# Vref.net
KiCad netlist of a schematic drawn in Altium Designer
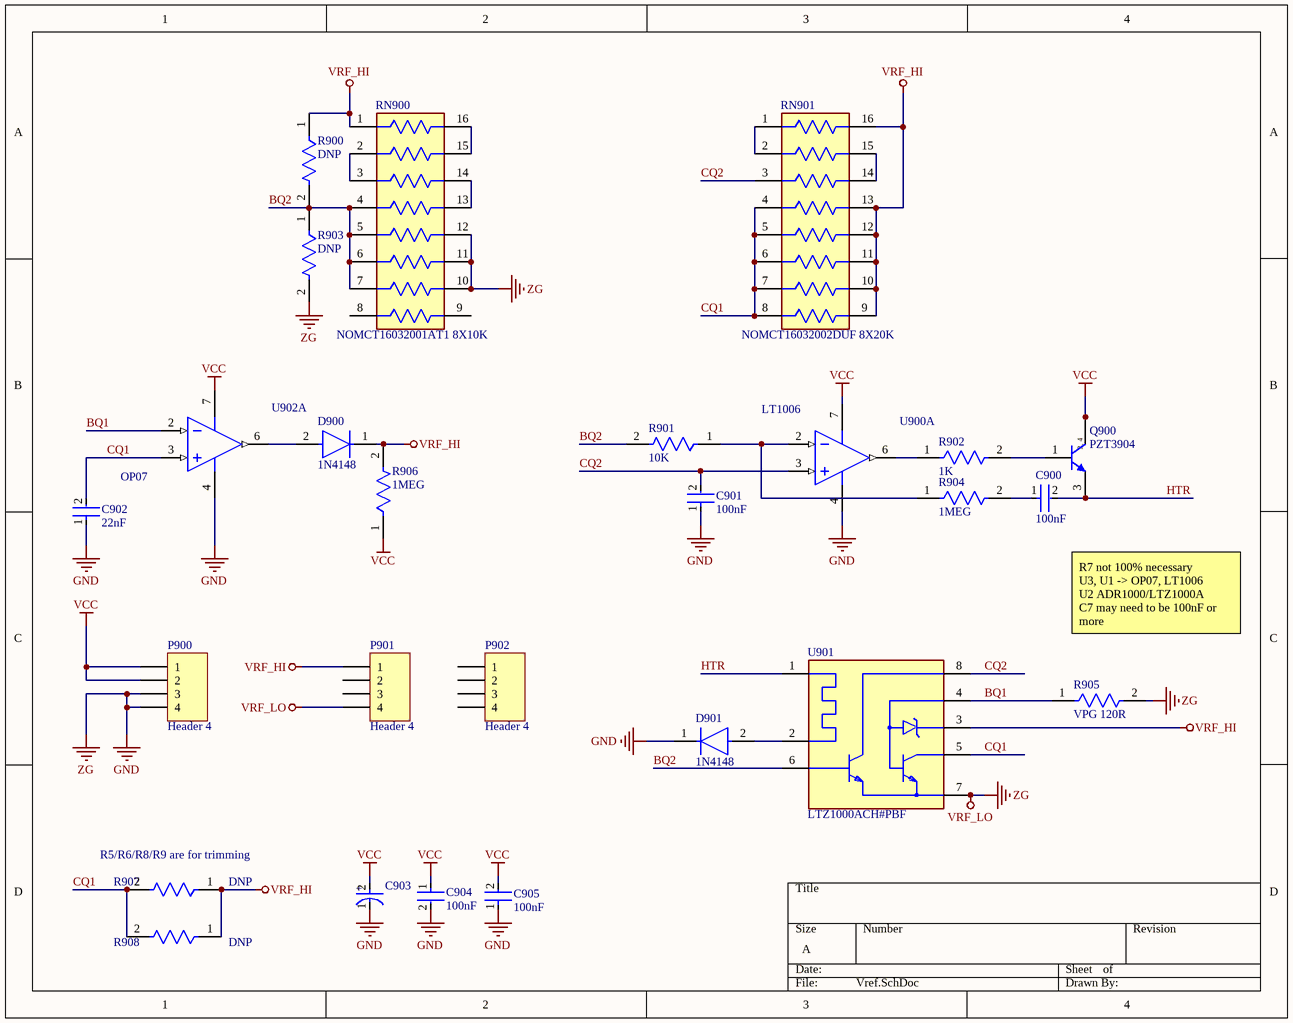
[diagram p0: Vref.SchDoc]

(export (version "E")
  (design (tool "Eeschema 10.0.6"))
  (components
    (comp (ref "C900")
      (value "100nF")
      (footprint "FP-CGA3E-0_3-0_1-IPC_B")
      (description "Cap Ceramic 100nF 50V X7R 10% Pad SMD 0603 +125°C Automotive T/R")
      (fields (field (name "TOLERANCE") "10%") (field (name "VOLTAGE") "50V"))
      (libsource (lib "Altium Content Vault") (part "b4654b650e69147ec39a6b967a45e02"))
    )
    (comp (ref "C901")
      (value "100nF")
      (footprint "FP-CGA3E-0_3-0_1-IPC_B")
      (description "Cap Ceramic 100nF 50V X7R 10% Pad SMD 0603 +125°C Automotive T/R")
      (fields (field (name "TOLERANCE") "10%") (field (name "VOLTAGE") "50V"))
      (libsource (lib "Altium Content Vault") (part "b4654b650e69147ec39a6b967a45e02"))
    )
    (comp (ref "C902")
      (value "22nF")
      (footprint "FP-CGA3E-0_3-0_1-IPC_B")
      (description "Cap Ceramic 100nF 50V X7R 10% Pad SMD 0603 +125°C Automotive T/R")
      (fields (field (name "TOLERANCE") "10%") (field (name "VOLTAGE") "50V"))
      (libsource (lib "Altium Content Vault") (part "b4654b650e69147ec39a6b967a45e02"))
    )
    (comp (ref "C903")
      (value "T491D226K025AT")
      (footprint "FP-T491D226K025AT-MFG")
      (description "CAP TANT 22UF 10% 25V 2917")
      (fields (field (name "TOLERANCE") "10%") (field (name "VOLTAGE") "25V"))
      (libsource (lib "Altium Content Vault") (part "a00bbbee19879c290e62620ae7e47b1"))
    )
    (comp (ref "C904")
      (value "100nF")
      (footprint "FP-CGA3E-0_3-0_1-IPC_B")
      (description "Cap Ceramic 100nF 50V X7R 10% Pad SMD 0603 +125°C Automotive T/R")
      (fields (field (name "TOLERANCE") "10%") (field (name "VOLTAGE") "50V"))
      (libsource (lib "Altium Content Vault") (part "b4654b650e69147ec39a6b967a45e02"))
    )
    (comp (ref "C905")
      (value "100nF")
      (footprint "FP-CGA3E-0_3-0_1-IPC_B")
      (description "Cap Ceramic 100nF 50V X7R 10% Pad SMD 0603 +125°C Automotive T/R")
      (fields (field (name "TOLERANCE") "10%") (field (name "VOLTAGE") "50V"))
      (libsource (lib "Altium Content Vault") (part "b4654b650e69147ec39a6b967a45e02"))
    )
    (comp (ref "D900")
      (value "1N4148")
      (footprint "FP-017AG-MFG")
      (description "DIODE GEN PURP 100V 200MA DO35")
      (fields (field (name "VOLTAGE") "100V"))
      (libsource (lib "Altium Content Vault") (part "d7152d700b627762746794eb795d46e"))
    )
    (comp (ref "D901")
      (value "1N4148")
      (footprint "FP-017AG-MFG")
      (description "DIODE GEN PURP 100V 200MA DO35")
      (fields (field (name "VOLTAGE") "100V"))
      (libsource (lib "Altium Content Vault") (part "d7152d700b627762746794eb795d46e"))
    )
    (comp (ref "P900")
      (value "Header 4")
      (footprint "HDR1X4")
      (description "Header, 4-Pin")
      (fields (field (name "PUBLISHER") "Altium Limited"))
      (libsource (lib "Miscellaneous Connectors") (part "Header 4"))
    )
    (comp (ref "P901")
      (value "Header 4")
      (footprint "HDR1X4")
      (description "Header, 4-Pin")
      (fields (field (name "PUBLISHER") "Altium Limited"))
      (libsource (lib "Miscellaneous Connectors") (part "Header 4"))
    )
    (comp (ref "P902")
      (value "Header 4")
      (footprint "HDR1X4")
      (description "Header, 4-Pin")
      (fields (field (name "PUBLISHER") "Altium Limited"))
      (libsource (lib "Miscellaneous Connectors") (part "Header 4"))
    )
    (comp (ref "Q900")
      (value "PZT3904")
      (footprint "FAIR-SOT223-4_V")
      (description "NPN General-Purpose Amplifier, 40 V, 200 mA, -55 to 150 degC, 4-Pin SOT223, RoHS, Tape and Reel")
      (fields (field (name "MANUFACTURER") "FairchildSemiconductor"))
      (libsource (lib "Altium Content Vault") (part "BJT-NPN-BCEC-4"))
    )
    (comp (ref "R900")
      (value "DNP")
      (footprint "FP-ERA3A-IPC_C")
      (description "RES SMD 1K OHM 0.1% 1/10W 0603")
      (fields (field (name "TOLERANCE") "0.1%"))
      (libsource (lib "Altium Content Vault") (part "1029c3af85768c4190bb7ad29bc67b5"))
    )
    (comp (ref "R901")
      (value "10K")
      (footprint "FP-ERA3A-IPC_C")
      (description "RES SMD 1K OHM 0.1% 1/10W 0603")
      (fields (field (name "TOLERANCE") "0.1%"))
      (libsource (lib "Altium Content Vault") (part "1029c3af85768c4190bb7ad29bc67b5"))
    )
    (comp (ref "R902")
      (value "1K")
      (footprint "FP-ERA3A-IPC_C")
      (description "RES SMD 1K OHM 0.1% 1/10W 0603")
      (fields (field (name "TOLERANCE") "0.1%"))
      (libsource (lib "Altium Content Vault") (part "1029c3af85768c4190bb7ad29bc67b5"))
    )
    (comp (ref "R903")
      (value "DNP")
      (footprint "FP-ERA3A-IPC_C")
      (description "RES SMD 1K OHM 0.1% 1/10W 0603")
      (fields (field (name "TOLERANCE") "0.1%"))
      (libsource (lib "Altium Content Vault") (part "1029c3af85768c4190bb7ad29bc67b5"))
    )
    (comp (ref "R904")
      (value "1MEG")
      (footprint "FP-CRCW0603-e3-IPC_A")
      (description "RES Thick Film, 1MΩ, 1%, 0.1W, 100ppm/°C, 0603")
      (fields (field (name "TOLERANCE") "1%"))
      (libsource (lib "Altium Content Vault") (part "1029c3af85768c4190bb7ad29bc67b5"))
    )
    (comp (ref "R905")
      (value "VPG 120R")
      (footprint "FP-S102K-MFG")
      (description "RES 20K OHM 0.6W 0.01% RADIAL")
      (fields (field (name "TOLERANCE") "0.01%"))
      (libsource (lib "Altium Content Vault") (part "1029c3af85768c4190bb7ad29bc67b5"))
    )
    (comp (ref "R906")
      (value "1MEG")
      (footprint "FP-CRCW0603-e3-IPC_A")
      (description "RES Thick Film, 1MΩ, 1%, 0.1W, 100ppm/°C, 0603")
      (fields (field (name "TOLERANCE") "1%"))
      (libsource (lib "Altium Content Vault") (part "1029c3af85768c4190bb7ad29bc67b5"))
    )
    (comp (ref "R907")
      (value "DNP")
      (footprint "FP-ERA3A-IPC_C")
      (description "RES SMD 1K OHM 0.1% 1/10W 0603")
      (fields (field (name "TOLERANCE") "0.1%"))
      (libsource (lib "Altium Content Vault") (part "1029c3af85768c4190bb7ad29bc67b5"))
    )
    (comp (ref "R908")
      (value "DNP")
      (footprint "FP-ERA3A-IPC_C")
      (description "RES SMD 1K OHM 0.1% 1/10W 0603")
      (fields (field (name "TOLERANCE") "0.1%"))
      (libsource (lib "Altium Content Vault") (part "1029c3af85768c4190bb7ad29bc67b5"))
    )
    (comp (ref "RN900")
      (value "NOMCT16032001AT1 8X10K")
      (footprint "FP-TDP16-MFG")
      (description "Res Thin Film NET 100K Ohm 0.5% 4/5W ±25ppm/°C ISOL Molded 16-Pin DIP Pin Thru-Hole Tube")
      (libsource (lib "Altium Content Vault") (part "611a6c6b9749f05368e044a25809b35"))
    )
    (comp (ref "RN901")
      (value "NOMCT16032002DUF 8X20K")
      (footprint "FP-TDP16-MFG")
      (description "Res Thin Film NET 100K Ohm 0.5% 4/5W ±25ppm/°C ISOL Molded 16-Pin DIP Pin Thru-Hole Tube")
      (libsource (lib "Altium Content Vault") (part "611a6c6b9749f05368e044a25809b35"))
    )
    (comp (ref "U900")
      (value "LT1006")
      (footprint "D0008A_M")
      (fields (field (name "MANUFACTURER") "Texas Instruments") (field (name "PARTNUMBER") "OPA140AID"))
      (libsource (lib "Altium Content Vault") (part "TI-OPA-8_1"))
    )
    (comp (ref "U901")
      (value "LTZ1000ACH#PBF")
      (footprint "FP-H-8-05-08-1320-MFG")
      (description "IC VREF SHUNT 7.2V TO5")
      (fields
        (field (name "OCTOPART") "https://octopart.com/ltz1000ach%23pbf-analog+devices-88320833")
        (field (name "MANUFACTURER") "Analog Devices")
      )
      (libsource (lib "Altium Content Vault") (part "226323f01f0396e9e7a43ae420630c2"))
    )
    (comp (ref "U902")
      (value "OP07")
      (footprint "D0008A_M")
      (fields (field (name "MANUFACTURER") "Texas Instruments") (field (name "PARTNUMBER") "OPA140AID"))
      (libsource (lib "Altium Content Vault") (part "TI-OPA-8_1"))
    )
  )
  (nets
    (net (code "1") (name "/BQ1") (class "Default")
      (node (ref "R905") (pin "1") (pinfunction "1_1") (pintype "passive"))
      (node (ref "U901") (pin "4") (pinfunction "SUBSTRATE/ZENER-_4") (pintype "passive"))
      (node (ref "U902") (pin "2") (pinfunction "IN-_2") (pintype "input"))
    )
    (net (code "2") (name "/BQ2") (class "Default")
      (node (ref "R900") (pin "2") (pinfunction "2_2") (pintype "passive"))
      (node (ref "R901") (pin "2") (pinfunction "2_2") (pintype "passive"))
      (node (ref "R903") (pin "1") (pinfunction "1_1") (pintype "passive"))
      (node (ref "RN900") (pin "4") (pinfunction "4_4") (pintype "passive"))
      (node (ref "RN900") (pin "5") (pinfunction "5_5") (pintype "passive"))
      (node (ref "RN900") (pin "6") (pinfunction "6_6") (pintype "passive"))
      (node (ref "RN900") (pin "7") (pinfunction "7_7") (pintype "passive"))
      (node (ref "U901") (pin "6") (pinfunction "B_6") (pintype "passive"))
    )
    (net (code "3") (name "/CQ1") (class "Default")
      (node (ref "C902") (pin "2") (pinfunction "2_2") (pintype "passive"))
      (node (ref "R907") (pin "2") (pinfunction "2_2") (pintype "passive"))
      (node (ref "R908") (pin "2") (pinfunction "2_2") (pintype "passive"))
      (node (ref "RN901") (pin "4") (pinfunction "4_4") (pintype "passive"))
      (node (ref "RN901") (pin "5") (pinfunction "5_5") (pintype "passive"))
      (node (ref "RN901") (pin "6") (pinfunction "6_6") (pintype "passive"))
      (node (ref "RN901") (pin "7") (pinfunction "7_7") (pintype "passive"))
      (node (ref "RN901") (pin "8") (pinfunction "8_8") (pintype "passive"))
      (node (ref "U901") (pin "5") (pinfunction "C_5") (pintype "passive"))
      (node (ref "U902") (pin "3") (pinfunction "IN+_3") (pintype "input"))
    )
    (net (code "4") (name "/CQ2") (class "Default")
      (node (ref "C901") (pin "2") (pinfunction "2_2") (pintype "passive"))
      (node (ref "RN901") (pin "3") (pinfunction "3_3") (pintype "passive"))
      (node (ref "U900") (pin "3") (pinfunction "IN+_3") (pintype "input"))
      (node (ref "U901") (pin "8") (pinfunction "C_8") (pintype "passive"))
    )
    (net (code "5") (name "/HTR") (class "Default")
      (node (ref "C900") (pin "2") (pinfunction "2_2") (pintype "passive"))
      (node (ref "Q900") (pin "3") (pinfunction "E_3") (pintype "passive"))
      (node (ref "U901") (pin "1") (pinfunction "HEATER+_1") (pintype "passive"))
    )
    (net (code "6") (name "GND") (class "Default")
      (node (ref "C901") (pin "1") (pinfunction "1_1") (pintype "passive"))
      (node (ref "C902") (pin "1") (pinfunction "1_1") (pintype "passive"))
      (node (ref "C903") (pin "1") (pinfunction "C_1") (pintype "passive"))
      (node (ref "C904") (pin "2") (pinfunction "2_2") (pintype "passive"))
      (node (ref "C905") (pin "1") (pinfunction "1_1") (pintype "passive"))
      (node (ref "D901") (pin "1") (pinfunction "C_1") (pintype "passive"))
      (node (ref "P900") (pin "3") (pinfunction "3_3") (pintype "passive"))
      (node (ref "P900") (pin "4") (pinfunction "4_4") (pintype "passive"))
      (node (ref "P901") (pin "4") (pinfunction "4_4") (pintype "passive"))
      (node (ref "R903") (pin "2") (pinfunction "2_2") (pintype "passive"))
      (node (ref "R905") (pin "2") (pinfunction "2_2") (pintype "passive"))
      (node (ref "RN900") (pin "10") (pinfunction "10_10") (pintype "passive"))
      (node (ref "RN900") (pin "11") (pinfunction "11_11") (pintype "passive"))
      (node (ref "RN900") (pin "12") (pinfunction "12_12") (pintype "passive"))
      (node (ref "U900") (pin "4") (pinfunction "V-_4") (pintype "power_in"))
      (node (ref "U901") (pin "7") (pinfunction "E_7") (pintype "passive"))
      (node (ref "U902") (pin "4") (pinfunction "V-_4") (pintype "power_in"))
    )
    (net (code "7") (name "Net-(C900-Pad1)") (class "Default")
      (node (ref "C900") (pin "1") (pinfunction "1_1") (pintype "passive"))
      (node (ref "R904") (pin "2") (pinfunction "2_2") (pintype "passive"))
    )
    (net (code "8") (name "Net-(D900-A)") (class "Default")
      (node (ref "D900") (pin "2") (pinfunction "A_2") (pintype "passive"))
      (node (ref "U902") (pin "6") (pinfunction "OUT_6") (pintype "output"))
    )
    (net (code "9") (name "Net-(D901-A)") (class "Default")
      (node (ref "D901") (pin "2") (pinfunction "A_2") (pintype "passive"))
      (node (ref "U901") (pin "2") (pinfunction "HEATER-_2") (pintype "passive"))
    )
    (net (code "10") (name "Net-(Q900-B)") (class "Default")
      (node (ref "Q900") (pin "1") (pinfunction "B_1") (pintype "passive"))
      (node (ref "R902") (pin "2") (pinfunction "2_2") (pintype "passive"))
    )
    (net (code "11") (name "Net-(RN900-Pad2)") (class "Default")
      (node (ref "RN900") (pin "2") (pinfunction "2_2") (pintype "passive"))
      (node (ref "RN900") (pin "3") (pinfunction "3_3") (pintype "passive"))
    )
    (net (code "12") (name "Net-(RN900-Pad13)") (class "Default")
      (node (ref "RN900") (pin "13") (pinfunction "13_13") (pintype "passive"))
      (node (ref "RN900") (pin "14") (pinfunction "14_14") (pintype "passive"))
    )
    (net (code "13") (name "Net-(RN900-Pad15)") (class "Default")
      (node (ref "RN900") (pin "15") (pinfunction "15_15") (pintype "passive"))
      (node (ref "RN900") (pin "16") (pinfunction "16_16") (pintype "passive"))
    )
    (net (code "14") (name "Net-(RN901-Pad1)") (class "Default")
      (node (ref "RN901") (pin "1") (pinfunction "1_1") (pintype "passive"))
      (node (ref "RN901") (pin "2") (pinfunction "2_2") (pintype "passive"))
    )
    (net (code "15") (name "Net-(RN901-Pad14)") (class "Default")
      (node (ref "RN901") (pin "14") (pinfunction "14_14") (pintype "passive"))
      (node (ref "RN901") (pin "15") (pinfunction "15_15") (pintype "passive"))
    )
    (net (code "16") (name "Net-(U900A-IN-)") (class "Default")
      (node (ref "R901") (pin "1") (pinfunction "1_1") (pintype "passive"))
      (node (ref "R904") (pin "1") (pinfunction "1_1") (pintype "passive"))
      (node (ref "U900") (pin "2") (pinfunction "IN-_2") (pintype "input"))
    )
    (net (code "17") (name "Net-(U900A-OUT)") (class "Default")
      (node (ref "R902") (pin "1") (pinfunction "1_1") (pintype "passive"))
      (node (ref "U900") (pin "6") (pinfunction "OUT_6") (pintype "output"))
    )
    (net (code "18") (name "VCC") (class "Default")
      (node (ref "C903") (pin "2") (pinfunction "A_2") (pintype "passive"))
      (node (ref "C904") (pin "1") (pinfunction "1_1") (pintype "passive"))
      (node (ref "C905") (pin "2") (pinfunction "2_2") (pintype "passive"))
      (node (ref "P900") (pin "1") (pinfunction "1_1") (pintype "passive"))
      (node (ref "P900") (pin "2") (pinfunction "2_2") (pintype "passive"))
      (node (ref "Q900") (pin "2") (pinfunction "C_2") (pintype "passive"))
      (node (ref "Q900") (pin "4") (pinfunction "C_4") (pintype "passive"))
      (node (ref "R906") (pin "1") (pinfunction "1_1") (pintype "passive"))
      (node (ref "U900") (pin "7") (pinfunction "V+_7") (pintype "power_in"))
      (node (ref "U902") (pin "7") (pinfunction "V+_7") (pintype "power_in"))
    )
    (net (code "19") (name "VRF_HI") (class "Default")
      (node (ref "D900") (pin "1") (pinfunction "C_1") (pintype "passive"))
      (node (ref "P901") (pin "1") (pinfunction "1_1") (pintype "passive"))
      (node (ref "R900") (pin "1") (pinfunction "1_1") (pintype "passive"))
      (node (ref "R906") (pin "2") (pinfunction "2_2") (pintype "passive"))
      (node (ref "R907") (pin "1") (pinfunction "1_1") (pintype "passive"))
      (node (ref "R908") (pin "1") (pinfunction "1_1") (pintype "passive"))
      (node (ref "RN900") (pin "1") (pinfunction "1_1") (pintype "passive"))
      (node (ref "RN901") (pin "10") (pinfunction "10_10") (pintype "passive"))
      (node (ref "RN901") (pin "11") (pinfunction "11_11") (pintype "passive"))
      (node (ref "RN901") (pin "12") (pinfunction "12_12") (pintype "passive"))
      (node (ref "RN901") (pin "13") (pinfunction "13_13") (pintype "passive"))
      (node (ref "RN901") (pin "16") (pinfunction "16_16") (pintype "passive"))
      (node (ref "RN901") (pin "9") (pinfunction "9_9") (pintype "passive"))
      (node (ref "U901") (pin "3") (pinfunction "ZENER+_3") (pintype "passive"))
    )
    (net (code "20") (name "unconnected-(P901-Pad2)") (class "Default")
      (node (ref "P901") (pin "2") (pinfunction "2_2") (pintype "passive"))
    )
    (net (code "21") (name "unconnected-(P901-Pad3)") (class "Default")
      (node (ref "P901") (pin "3") (pinfunction "3_3") (pintype "passive"))
    )
    (net (code "22") (name "unconnected-(P902-Pad1)") (class "Default")
      (node (ref "P902") (pin "1") (pinfunction "1_1") (pintype "passive"))
    )
    (net (code "23") (name "unconnected-(P902-Pad2)") (class "Default")
      (node (ref "P902") (pin "2") (pinfunction "2_2") (pintype "passive"))
    )
    (net (code "24") (name "unconnected-(P902-Pad3)") (class "Default")
      (node (ref "P902") (pin "3") (pinfunction "3_3") (pintype "passive"))
    )
    (net (code "25") (name "unconnected-(P902-Pad4)") (class "Default")
      (node (ref "P902") (pin "4") (pinfunction "4_4") (pintype "passive"))
    )
    (net (code "26") (name "unconnected-(RN900-Pad8)") (class "Default")
      (node (ref "RN900") (pin "8") (pinfunction "8_8") (pintype "passive"))
    )
    (net (code "27") (name "unconnected-(RN900-Pad9)") (class "Default")
      (node (ref "RN900") (pin "9") (pinfunction "9_9") (pintype "passive"))
    )
  )
)
